# v_da-detector-v2.net
KiCad netlist of a schematic drawn in EasyEDA Pro
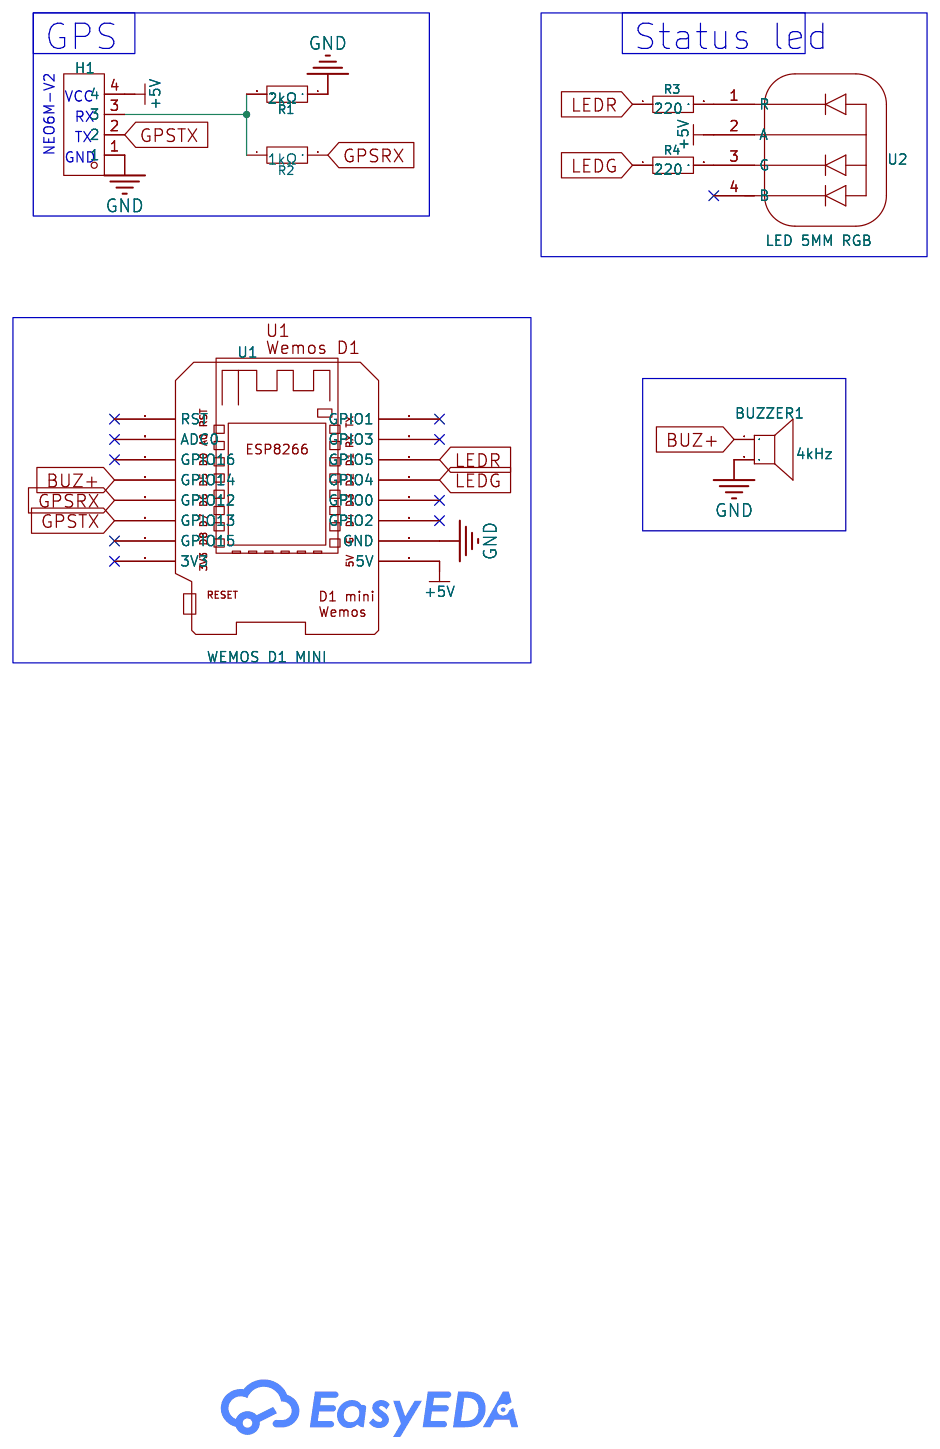
[diagram p0: schematic sheet]

(export (version "E")
  (design (tool "Eeschema 10.0.6"))
  (components
    (comp (ref "BUZZER1")
      (value "4kHz")
      (footprint "easyedapro:BUZ-TH_BD12.5-P6.50-D0.9")
      (fields (field (name "Manufacturer Part") "SFN-1207PA6.5") (field (name "Manufacturer") "S&S(海旭)"))
      (libsource (lib "easyedapro") (part "SFN-1207PA6.5"))
    )
    (comp (ref "H1")
      (value "~")
      (footprint "easyedapro:HDR-TH_4P-P2.54-V-M")
      (libsource (lib "easyedapro") (part "PZ254V-11-04P"))
    )
    (comp (ref "R1")
      (value "2kΩ")
      (footprint "easyedapro:R0805")
      (fields
        (field (name "Manufacturer Part") "0805W8F1002T5E")
        (field (name "Manufacturer") "UNI-ROYAL(厚声)")
      )
      (libsource (lib "easyedapro") (part "0805W8F1002T5E"))
    )
    (comp (ref "R2")
      (value "1kΩ")
      (footprint "easyedapro:R0805")
      (fields
        (field (name "Manufacturer Part") "0805W8F1002T5E")
        (field (name "Manufacturer") "UNI-ROYAL(厚声)")
      )
      (libsource (lib "easyedapro") (part "0805W8F1002T5E"))
    )
    (comp (ref "R3")
      (value "220")
      (footprint "easyedapro:R0805")
      (fields
        (field (name "Manufacturer Part") "0805W8F1002T5E")
        (field (name "Manufacturer") "UNI-ROYAL(厚声)")
      )
      (libsource (lib "easyedapro") (part "0805W8F1002T5E"))
    )
    (comp (ref "R4")
      (value "220")
      (footprint "easyedapro:R0805")
      (fields
        (field (name "Manufacturer Part") "0805W8F1002T5E")
        (field (name "Manufacturer") "UNI-ROYAL(厚声)")
      )
      (libsource (lib "easyedapro") (part "0805W8F1002T5E"))
    )
    (comp (ref "U1")
      (value "WEMOS D1 MINI")
      (footprint "easyedapro:WEMOS-D1-MINI")
      (libsource (lib "easyedapro") (part "WEMOS D1 MINI"))
    )
    (comp (ref "U2")
      (value "LED 5MM RGB")
      (footprint "easyedapro:LED 5MM RGB TH")
      (libsource (lib "easyedapro") (part "LED 5MM RGB"))
    )
  )
  (nets
    (net (code "1") (name "+5V") (class "Default")
      (node (ref "H1") (pin "4") (pinfunction "4_4") (pintype "unspecified"))
      (node (ref "U1") (pin "5V") (pinfunction "5V_5V") (pintype "unspecified"))
      (node (ref "U2") (pin "2") (pinfunction "A_2") (pintype "unspecified"))
    )
    (net (code "2") (name "BUZ+") (class "Default")
      (node (ref "BUZZER1") (pin "1") (pinfunction "1_1") (pintype "unspecified"))
      (node (ref "U1") (pin "D5") (pinfunction "GPIO14_D5") (pintype "bidirectional"))
    )
    (net (code "3") (name "GND") (class "Default")
      (node (ref "BUZZER1") (pin "2") (pinfunction "2_2") (pintype "unspecified"))
      (node (ref "H1") (pin "1") (pinfunction "1_1") (pintype "unspecified"))
      (node (ref "R1") (pin "1") (pinfunction "1_1") (pintype "input"))
      (node (ref "U1") (pin "GND") (pinfunction "GND_GND") (pintype "unspecified"))
    )
    (net (code "4") (name "GPSRX") (class "Default")
      (node (ref "R2") (pin "2") (pinfunction "2_2") (pintype "input"))
      (node (ref "U1") (pin "D6") (pinfunction "GPIO12_D6") (pintype "bidirectional"))
    )
    (net (code "5") (name "GPSTX") (class "Default")
      (node (ref "H1") (pin "2") (pinfunction "2_2") (pintype "unspecified"))
      (node (ref "U1") (pin "D7") (pinfunction "GPIO13_D7") (pintype "bidirectional"))
    )
    (net (code "6") (name "LEDG") (class "Default")
      (node (ref "R4") (pin "1") (pinfunction "1_1") (pintype "input"))
      (node (ref "U1") (pin "D2") (pinfunction "GPIO4_D2") (pintype "bidirectional"))
    )
    (net (code "7") (name "LEDR") (class "Default")
      (node (ref "R3") (pin "1") (pinfunction "1_1") (pintype "input"))
      (node (ref "U1") (pin "D1") (pinfunction "GPIO5_D1") (pintype "bidirectional"))
    )
    (net (code "8") (name "Net-(H1-Pad3)") (class "Default")
      (node (ref "H1") (pin "3") (pinfunction "3_3") (pintype "unspecified"))
      (node (ref "R1") (pin "2") (pinfunction "2_2") (pintype "input"))
      (node (ref "R2") (pin "1") (pinfunction "1_1") (pintype "input"))
    )
    (net (code "9") (name "Net-(U2-G)") (class "Default")
      (node (ref "R4") (pin "2") (pinfunction "2_2") (pintype "input"))
      (node (ref "U2") (pin "3") (pinfunction "G_3") (pintype "unspecified"))
    )
    (net (code "10") (name "Net-(U2-R)") (class "Default")
      (node (ref "R3") (pin "2") (pinfunction "2_2") (pintype "input"))
      (node (ref "U2") (pin "1") (pinfunction "R_1") (pintype "unspecified"))
    )
    (net (code "11") (name "unconnected-(U1-ADC0-PadA0)") (class "Default")
      (node (ref "U1") (pin "A0") (pinfunction "ADC0_A0") (pintype "input+no_connect"))
    )
    (net (code "12") (name "unconnected-(U1-GPIO0-PadD3)") (class "Default")
      (node (ref "U1") (pin "D3") (pinfunction "GPIO0_D3") (pintype "bidirectional+no_connect"))
    )
    (net (code "13") (name "unconnected-(U1-GPIO1-PadTX)") (class "Default")
      (node (ref "U1") (pin "TX") (pinfunction "GPIO1_TX") (pintype "bidirectional+no_connect"))
    )
    (net (code "14") (name "unconnected-(U1-GPIO2-PadD4)") (class "Default")
      (node (ref "U1") (pin "D4") (pinfunction "GPIO2_D4") (pintype "bidirectional+no_connect"))
    )
    (net (code "15") (name "unconnected-(U1-GPIO3-PadRX)") (class "Default")
      (node (ref "U1") (pin "RX") (pinfunction "GPIO3_RX") (pintype "bidirectional+no_connect"))
    )
    (net (code "16") (name "unconnected-(U1-GPIO15-PadD8)") (class "Default")
      (node (ref "U1") (pin "D8") (pinfunction "GPIO15_D8") (pintype "bidirectional+no_connect"))
    )
    (net (code "17") (name "unconnected-(U1-GPIO16-PadD0)") (class "Default")
      (node (ref "U1") (pin "D0") (pinfunction "GPIO16_D0") (pintype "bidirectional+no_connect"))
    )
    (net (code "18") (name "unconnected-(U1-Pad3V3)") (class "Default")
      (node (ref "U1") (pin "3V3") (pinfunction "3V3_3V3") (pintype "unspecified+no_connect"))
    )
    (net (code "19") (name "unconnected-(U1-PadRST)") (class "Default")
      (node (ref "U1") (pin "RST") (pinfunction "RST_RST") (pintype "input+no_connect"))
    )
    (net (code "20") (name "unconnected-(U2-B-Pad4)") (class "Default")
      (node (ref "U2") (pin "4") (pinfunction "B_4") (pintype "unspecified+no_connect"))
    )
  )
)
